# riaa_pre.net
KiCad netlist of a schematic drawn in EAGLE
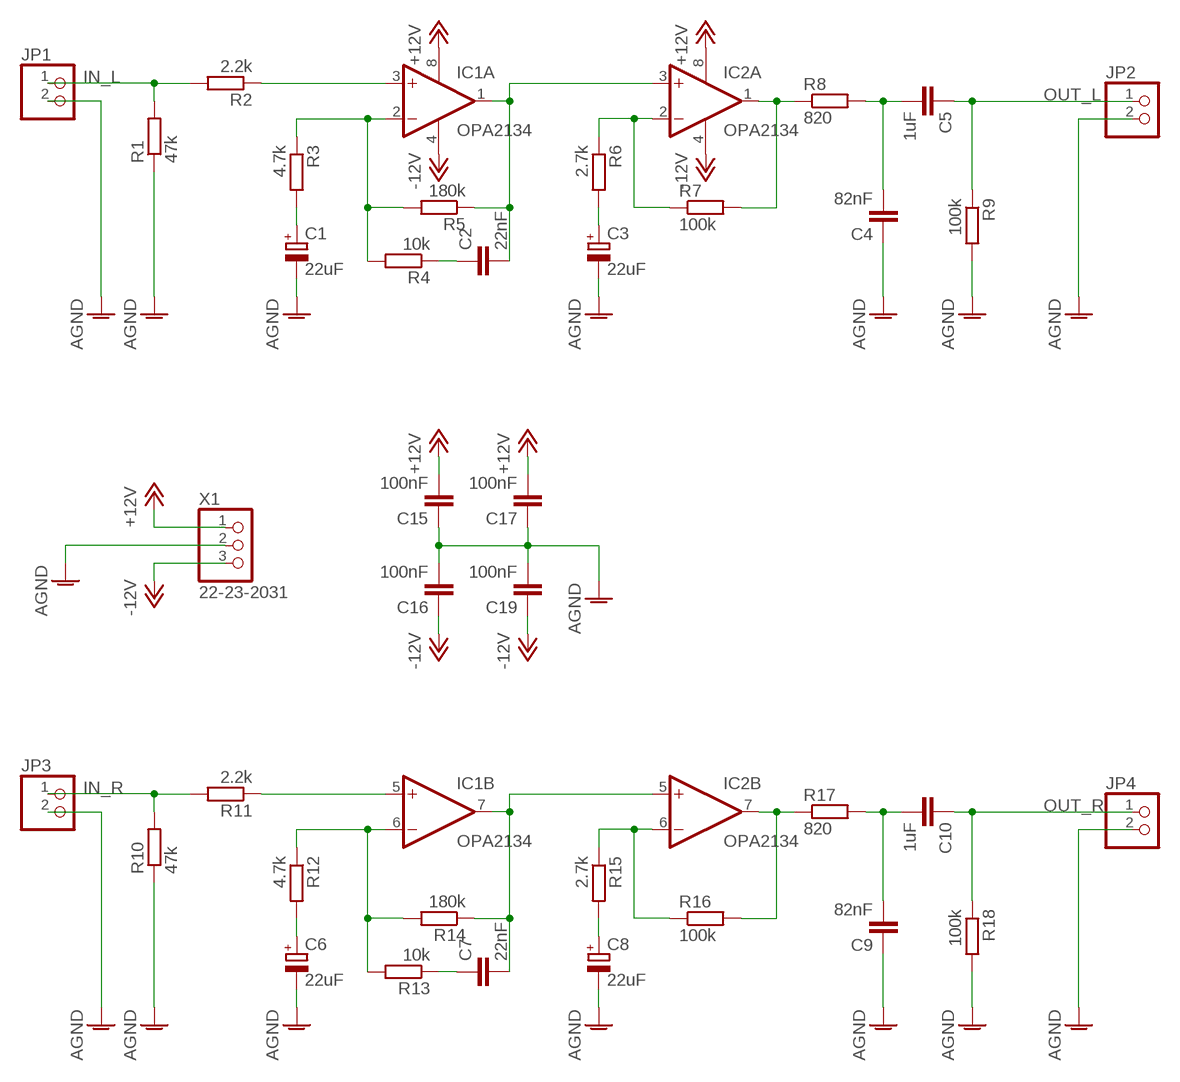
[diagram p0: schematic, sheet 1]

(export (version "E")
  (design (tool "Eeschema 10.0.6"))
  (components
    (comp (ref "C1")
      (value "22uF")
      (footprint "eagle-import:E2,5-6")
      (libsource (lib "eagle-import") (part "CPOL-EUE2.5-6"))
    )
    (comp (ref "C2")
      (value "22nF")
      (footprint "eagle-import:C050-025X075")
      (libsource (lib "eagle-import") (part "C-EU050-025X075"))
    )
    (comp (ref "C3")
      (value "22uF")
      (footprint "eagle-import:E2,5-6")
      (libsource (lib "eagle-import") (part "CPOL-EUE2.5-6"))
    )
    (comp (ref "C4")
      (value "82nF")
      (footprint "eagle-import:C050-025X075")
      (libsource (lib "eagle-import") (part "C-EU050-025X075"))
    )
    (comp (ref "C5")
      (value "1uF")
      (footprint "eagle-import:C050-045X075")
      (libsource (lib "eagle-import") (part "C-EU050-045X075"))
    )
    (comp (ref "C6")
      (value "22uF")
      (footprint "eagle-import:E2,5-6")
      (libsource (lib "eagle-import") (part "CPOL-EUE2.5-6"))
    )
    (comp (ref "C7")
      (value "22nF")
      (footprint "eagle-import:C050-025X075")
      (libsource (lib "eagle-import") (part "C-EU050-025X075"))
    )
    (comp (ref "C8")
      (value "22uF")
      (footprint "eagle-import:E2,5-6")
      (libsource (lib "eagle-import") (part "CPOL-EUE2.5-6"))
    )
    (comp (ref "C9")
      (value "82nF")
      (footprint "eagle-import:C050-025X075")
      (libsource (lib "eagle-import") (part "C-EU050-025X075"))
    )
    (comp (ref "C10")
      (value "1uF")
      (footprint "eagle-import:C050-045X075")
      (libsource (lib "eagle-import") (part "C-EU050-045X075"))
    )
    (comp (ref "C15")
      (value "100nF")
      (footprint "eagle-import:C050-025X075")
      (libsource (lib "eagle-import") (part "C-EU050-025X075"))
    )
    (comp (ref "C16")
      (value "100nF")
      (footprint "eagle-import:C050-025X075")
      (libsource (lib "eagle-import") (part "C-EU050-025X075"))
    )
    (comp (ref "C17")
      (value "100nF")
      (footprint "eagle-import:C050-025X075")
      (libsource (lib "eagle-import") (part "C-EU050-025X075"))
    )
    (comp (ref "C19")
      (value "100nF")
      (footprint "eagle-import:C050-025X075")
      (libsource (lib "eagle-import") (part "C-EU050-025X075"))
    )
    (comp (ref "IC1")
      (value "OPA2134")
      (footprint "eagle-import:DIL08")
      (libsource (lib "eagle-import") (part "OPA2PA134"))
    )
    (comp (ref "IC2")
      (value "OPA2134")
      (footprint "eagle-import:DIL08")
      (libsource (lib "eagle-import") (part "OPA2PA134"))
    )
    (comp (ref "JP1")
      (value "PINHD-1X2")
      (footprint "eagle-import:1X02")
      (libsource (lib "eagle-import") (part "PINHD-1X2"))
    )
    (comp (ref "JP2")
      (value "PINHD-1X2")
      (footprint "eagle-import:1X02")
      (libsource (lib "eagle-import") (part "PINHD-1X2"))
    )
    (comp (ref "JP3")
      (value "PINHD-1X2")
      (footprint "eagle-import:1X02")
      (libsource (lib "eagle-import") (part "PINHD-1X2"))
    )
    (comp (ref "JP4")
      (value "PINHD-1X2")
      (footprint "eagle-import:1X02")
      (libsource (lib "eagle-import") (part "PINHD-1X2"))
    )
    (comp (ref "R1")
      (value "47k")
      (footprint "eagle-import:0207_7")
      (libsource (lib "eagle-import") (part "R-EU_0207/7"))
    )
    (comp (ref "R2")
      (value "2.2k")
      (footprint "eagle-import:0207_7")
      (libsource (lib "eagle-import") (part "R-EU_0207/7"))
    )
    (comp (ref "R3")
      (value "4.7k")
      (footprint "eagle-import:0207_7")
      (libsource (lib "eagle-import") (part "R-EU_0207/7"))
    )
    (comp (ref "R4")
      (value "10k")
      (footprint "eagle-import:0207_7")
      (libsource (lib "eagle-import") (part "R-EU_0207/7"))
    )
    (comp (ref "R5")
      (value "180k")
      (footprint "eagle-import:0207_7")
      (libsource (lib "eagle-import") (part "R-EU_0207/7"))
    )
    (comp (ref "R6")
      (value "2.7k")
      (footprint "eagle-import:0207_7")
      (libsource (lib "eagle-import") (part "R-EU_0207/7"))
    )
    (comp (ref "R7")
      (value "100k")
      (footprint "eagle-import:0207_7")
      (libsource (lib "eagle-import") (part "R-EU_0207/7"))
    )
    (comp (ref "R8")
      (value "820")
      (footprint "eagle-import:0207_7")
      (libsource (lib "eagle-import") (part "R-EU_0207/7"))
    )
    (comp (ref "R9")
      (value "100k")
      (footprint "eagle-import:0207_7")
      (libsource (lib "eagle-import") (part "R-EU_0207/7"))
    )
    (comp (ref "R10")
      (value "47k")
      (footprint "eagle-import:0207_7")
      (libsource (lib "eagle-import") (part "R-EU_0207/7"))
    )
    (comp (ref "R11")
      (value "2.2k")
      (footprint "eagle-import:0207_7")
      (libsource (lib "eagle-import") (part "R-EU_0207/7"))
    )
    (comp (ref "R12")
      (value "4.7k")
      (footprint "eagle-import:0207_7")
      (libsource (lib "eagle-import") (part "R-EU_0207/7"))
    )
    (comp (ref "R13")
      (value "10k")
      (footprint "eagle-import:0207_7")
      (libsource (lib "eagle-import") (part "R-EU_0207/7"))
    )
    (comp (ref "R14")
      (value "180k")
      (footprint "eagle-import:0207_7")
      (libsource (lib "eagle-import") (part "R-EU_0207/7"))
    )
    (comp (ref "R15")
      (value "2.7k")
      (footprint "eagle-import:0207_7")
      (libsource (lib "eagle-import") (part "R-EU_0207/7"))
    )
    (comp (ref "R16")
      (value "100k")
      (footprint "eagle-import:0207_7")
      (libsource (lib "eagle-import") (part "R-EU_0207/7"))
    )
    (comp (ref "R17")
      (value "820")
      (footprint "eagle-import:0207_7")
      (libsource (lib "eagle-import") (part "R-EU_0207/7"))
    )
    (comp (ref "R18")
      (value "100k")
      (footprint "eagle-import:0207_7")
      (libsource (lib "eagle-import") (part "R-EU_0207/7"))
    )
    (comp (ref "X1")
      (value "22-23-2031")
      (footprint "eagle-import:22-23-2031")
      (libsource (lib "eagle-import") (part "22-23-2031"))
    )
  )
  (nets
    (net (code "1") (name "+12V") (class "Default")
      (node (ref "C15") (pin "2") (pinfunction "2_2") (pintype "passive"))
      (node (ref "C17") (pin "2") (pinfunction "2_2") (pintype "passive"))
      (node (ref "IC1") (pin "8") (pinfunction "V+_8") (pintype "power_in"))
      (node (ref "IC2") (pin "8") (pinfunction "V+_8") (pintype "power_in"))
      (node (ref "X1") (pin "1") (pinfunction "1_1") (pintype "passive"))
    )
    (net (code "2") (name "-12V") (class "Default")
      (node (ref "C16") (pin "1") (pinfunction "1_1") (pintype "passive"))
      (node (ref "C19") (pin "1") (pinfunction "1_1") (pintype "passive"))
      (node (ref "IC1") (pin "4") (pinfunction "V-_4") (pintype "power_in"))
      (node (ref "IC2") (pin "4") (pinfunction "V-_4") (pintype "power_in"))
      (node (ref "X1") (pin "3") (pinfunction "3_3") (pintype "passive"))
    )
    (net (code "3") (name "/IN_L") (class "Default")
      (node (ref "JP1") (pin "1") (pinfunction "1_1") (pintype "passive"))
      (node (ref "R1") (pin "2") (pinfunction "2_2") (pintype "passive"))
      (node (ref "R2") (pin "2") (pinfunction "2_2") (pintype "passive"))
    )
    (net (code "4") (name "/IN_R") (class "Default")
      (node (ref "JP3") (pin "1") (pinfunction "1_1") (pintype "passive"))
      (node (ref "R10") (pin "2") (pinfunction "2_2") (pintype "passive"))
      (node (ref "R11") (pin "2") (pinfunction "2_2") (pintype "passive"))
    )
    (net (code "5") (name "/OUT_L") (class "Default")
      (node (ref "C5") (pin "1") (pinfunction "1_1") (pintype "passive"))
      (node (ref "JP2") (pin "1") (pinfunction "1_1") (pintype "passive"))
      (node (ref "R9") (pin "1") (pinfunction "1_1") (pintype "passive"))
    )
    (net (code "6") (name "/OUT_R") (class "Default")
      (node (ref "C10") (pin "1") (pinfunction "1_1") (pintype "passive"))
      (node (ref "JP4") (pin "1") (pinfunction "1_1") (pintype "passive"))
      (node (ref "R18") (pin "1") (pinfunction "1_1") (pintype "passive"))
    )
    (net (code "7") (name "AGND") (class "Default")
      (node (ref "C1") (pin "-") (pinfunction "-_-") (pintype "passive"))
      (node (ref "C15") (pin "1") (pinfunction "1_1") (pintype "passive"))
      (node (ref "C16") (pin "2") (pinfunction "2_2") (pintype "passive"))
      (node (ref "C17") (pin "1") (pinfunction "1_1") (pintype "passive"))
      (node (ref "C19") (pin "2") (pinfunction "2_2") (pintype "passive"))
      (node (ref "C3") (pin "-") (pinfunction "-_-") (pintype "passive"))
      (node (ref "C4") (pin "1") (pinfunction "1_1") (pintype "passive"))
      (node (ref "C6") (pin "-") (pinfunction "-_-") (pintype "passive"))
      (node (ref "C8") (pin "-") (pinfunction "-_-") (pintype "passive"))
      (node (ref "C9") (pin "1") (pinfunction "1_1") (pintype "passive"))
      (node (ref "JP1") (pin "2") (pinfunction "2_2") (pintype "passive"))
      (node (ref "JP2") (pin "2") (pinfunction "2_2") (pintype "passive"))
      (node (ref "JP3") (pin "2") (pinfunction "2_2") (pintype "passive"))
      (node (ref "JP4") (pin "2") (pinfunction "2_2") (pintype "passive"))
      (node (ref "R1") (pin "1") (pinfunction "1_1") (pintype "passive"))
      (node (ref "R10") (pin "1") (pinfunction "1_1") (pintype "passive"))
      (node (ref "R18") (pin "2") (pinfunction "2_2") (pintype "passive"))
      (node (ref "R9") (pin "2") (pinfunction "2_2") (pintype "passive"))
      (node (ref "X1") (pin "2") (pinfunction "2_2") (pintype "passive"))
    )
    (net (code "8") (name "Net-(C1-Pad+)") (class "Default")
      (node (ref "C1") (pin "+") (pinfunction "+_+") (pintype "passive"))
      (node (ref "R3") (pin "2") (pinfunction "2_2") (pintype "passive"))
    )
    (net (code "9") (name "Net-(C2-Pad1)") (class "Default")
      (node (ref "C2") (pin "1") (pinfunction "1_1") (pintype "passive"))
      (node (ref "R4") (pin "1") (pinfunction "1_1") (pintype "passive"))
    )
    (net (code "10") (name "Net-(C3-Pad+)") (class "Default")
      (node (ref "C3") (pin "+") (pinfunction "+_+") (pintype "passive"))
      (node (ref "R6") (pin "2") (pinfunction "2_2") (pintype "passive"))
    )
    (net (code "11") (name "Net-(C4-Pad2)") (class "Default")
      (node (ref "C4") (pin "2") (pinfunction "2_2") (pintype "passive"))
      (node (ref "C5") (pin "2") (pinfunction "2_2") (pintype "passive"))
      (node (ref "R8") (pin "2") (pinfunction "2_2") (pintype "passive"))
    )
    (net (code "12") (name "Net-(C6-Pad+)") (class "Default")
      (node (ref "C6") (pin "+") (pinfunction "+_+") (pintype "passive"))
      (node (ref "R12") (pin "2") (pinfunction "2_2") (pintype "passive"))
    )
    (net (code "13") (name "Net-(C7-Pad1)") (class "Default")
      (node (ref "C7") (pin "1") (pinfunction "1_1") (pintype "passive"))
      (node (ref "R13") (pin "1") (pinfunction "1_1") (pintype "passive"))
    )
    (net (code "14") (name "Net-(C8-Pad+)") (class "Default")
      (node (ref "C8") (pin "+") (pinfunction "+_+") (pintype "passive"))
      (node (ref "R15") (pin "2") (pinfunction "2_2") (pintype "passive"))
    )
    (net (code "15") (name "Net-(C10-Pad2)") (class "Default")
      (node (ref "C10") (pin "2") (pinfunction "2_2") (pintype "passive"))
      (node (ref "C9") (pin "2") (pinfunction "2_2") (pintype "passive"))
      (node (ref "R17") (pin "2") (pinfunction "2_2") (pintype "passive"))
    )
    (net (code "16") (name "Net-(IC1A-+IN)") (class "Default")
      (node (ref "IC1") (pin "3") (pinfunction "+IN_3") (pintype "input"))
      (node (ref "R2") (pin "1") (pinfunction "1_1") (pintype "passive"))
    )
    (net (code "17") (name "Net-(IC1A--IN)") (class "Default")
      (node (ref "IC1") (pin "2") (pinfunction "-IN_2") (pintype "input"))
      (node (ref "R3") (pin "1") (pinfunction "1_1") (pintype "passive"))
      (node (ref "R4") (pin "2") (pinfunction "2_2") (pintype "passive"))
      (node (ref "R5") (pin "2") (pinfunction "2_2") (pintype "passive"))
    )
    (net (code "18") (name "Net-(IC1A-OUT)") (class "Default")
      (node (ref "C2") (pin "2") (pinfunction "2_2") (pintype "passive"))
      (node (ref "IC1") (pin "1") (pinfunction "OUT_1") (pintype "output"))
      (node (ref "IC2") (pin "3") (pinfunction "+IN_3") (pintype "input"))
      (node (ref "R5") (pin "1") (pinfunction "1_1") (pintype "passive"))
    )
    (net (code "19") (name "Net-(IC1B-+IN)") (class "Default")
      (node (ref "IC1") (pin "5") (pinfunction "+IN_5") (pintype "input"))
      (node (ref "R11") (pin "1") (pinfunction "1_1") (pintype "passive"))
    )
    (net (code "20") (name "Net-(IC1B--IN)") (class "Default")
      (node (ref "IC1") (pin "6") (pinfunction "-IN_6") (pintype "input"))
      (node (ref "R12") (pin "1") (pinfunction "1_1") (pintype "passive"))
      (node (ref "R13") (pin "2") (pinfunction "2_2") (pintype "passive"))
      (node (ref "R14") (pin "2") (pinfunction "2_2") (pintype "passive"))
    )
    (net (code "21") (name "Net-(IC1B-OUT)") (class "Default")
      (node (ref "C7") (pin "2") (pinfunction "2_2") (pintype "passive"))
      (node (ref "IC1") (pin "7") (pinfunction "OUT_7") (pintype "output"))
      (node (ref "IC2") (pin "5") (pinfunction "+IN_5") (pintype "input"))
      (node (ref "R14") (pin "1") (pinfunction "1_1") (pintype "passive"))
    )
    (net (code "22") (name "Net-(IC2A--IN)") (class "Default")
      (node (ref "IC2") (pin "2") (pinfunction "-IN_2") (pintype "input"))
      (node (ref "R6") (pin "1") (pinfunction "1_1") (pintype "passive"))
      (node (ref "R7") (pin "1") (pinfunction "1_1") (pintype "passive"))
    )
    (net (code "23") (name "Net-(IC2A-OUT)") (class "Default")
      (node (ref "IC2") (pin "1") (pinfunction "OUT_1") (pintype "output"))
      (node (ref "R7") (pin "2") (pinfunction "2_2") (pintype "passive"))
      (node (ref "R8") (pin "1") (pinfunction "1_1") (pintype "passive"))
    )
    (net (code "24") (name "Net-(IC2B--IN)") (class "Default")
      (node (ref "IC2") (pin "6") (pinfunction "-IN_6") (pintype "input"))
      (node (ref "R15") (pin "1") (pinfunction "1_1") (pintype "passive"))
      (node (ref "R16") (pin "1") (pinfunction "1_1") (pintype "passive"))
    )
    (net (code "25") (name "Net-(IC2B-OUT)") (class "Default")
      (node (ref "IC2") (pin "7") (pinfunction "OUT_7") (pintype "output"))
      (node (ref "R16") (pin "2") (pinfunction "2_2") (pintype "passive"))
      (node (ref "R17") (pin "1") (pinfunction "1_1") (pintype "passive"))
    )
  )
)
